# SCH_RDA5807FP_-__2024-04-29.net
KiCad netlist of a schematic drawn in EasyEDA
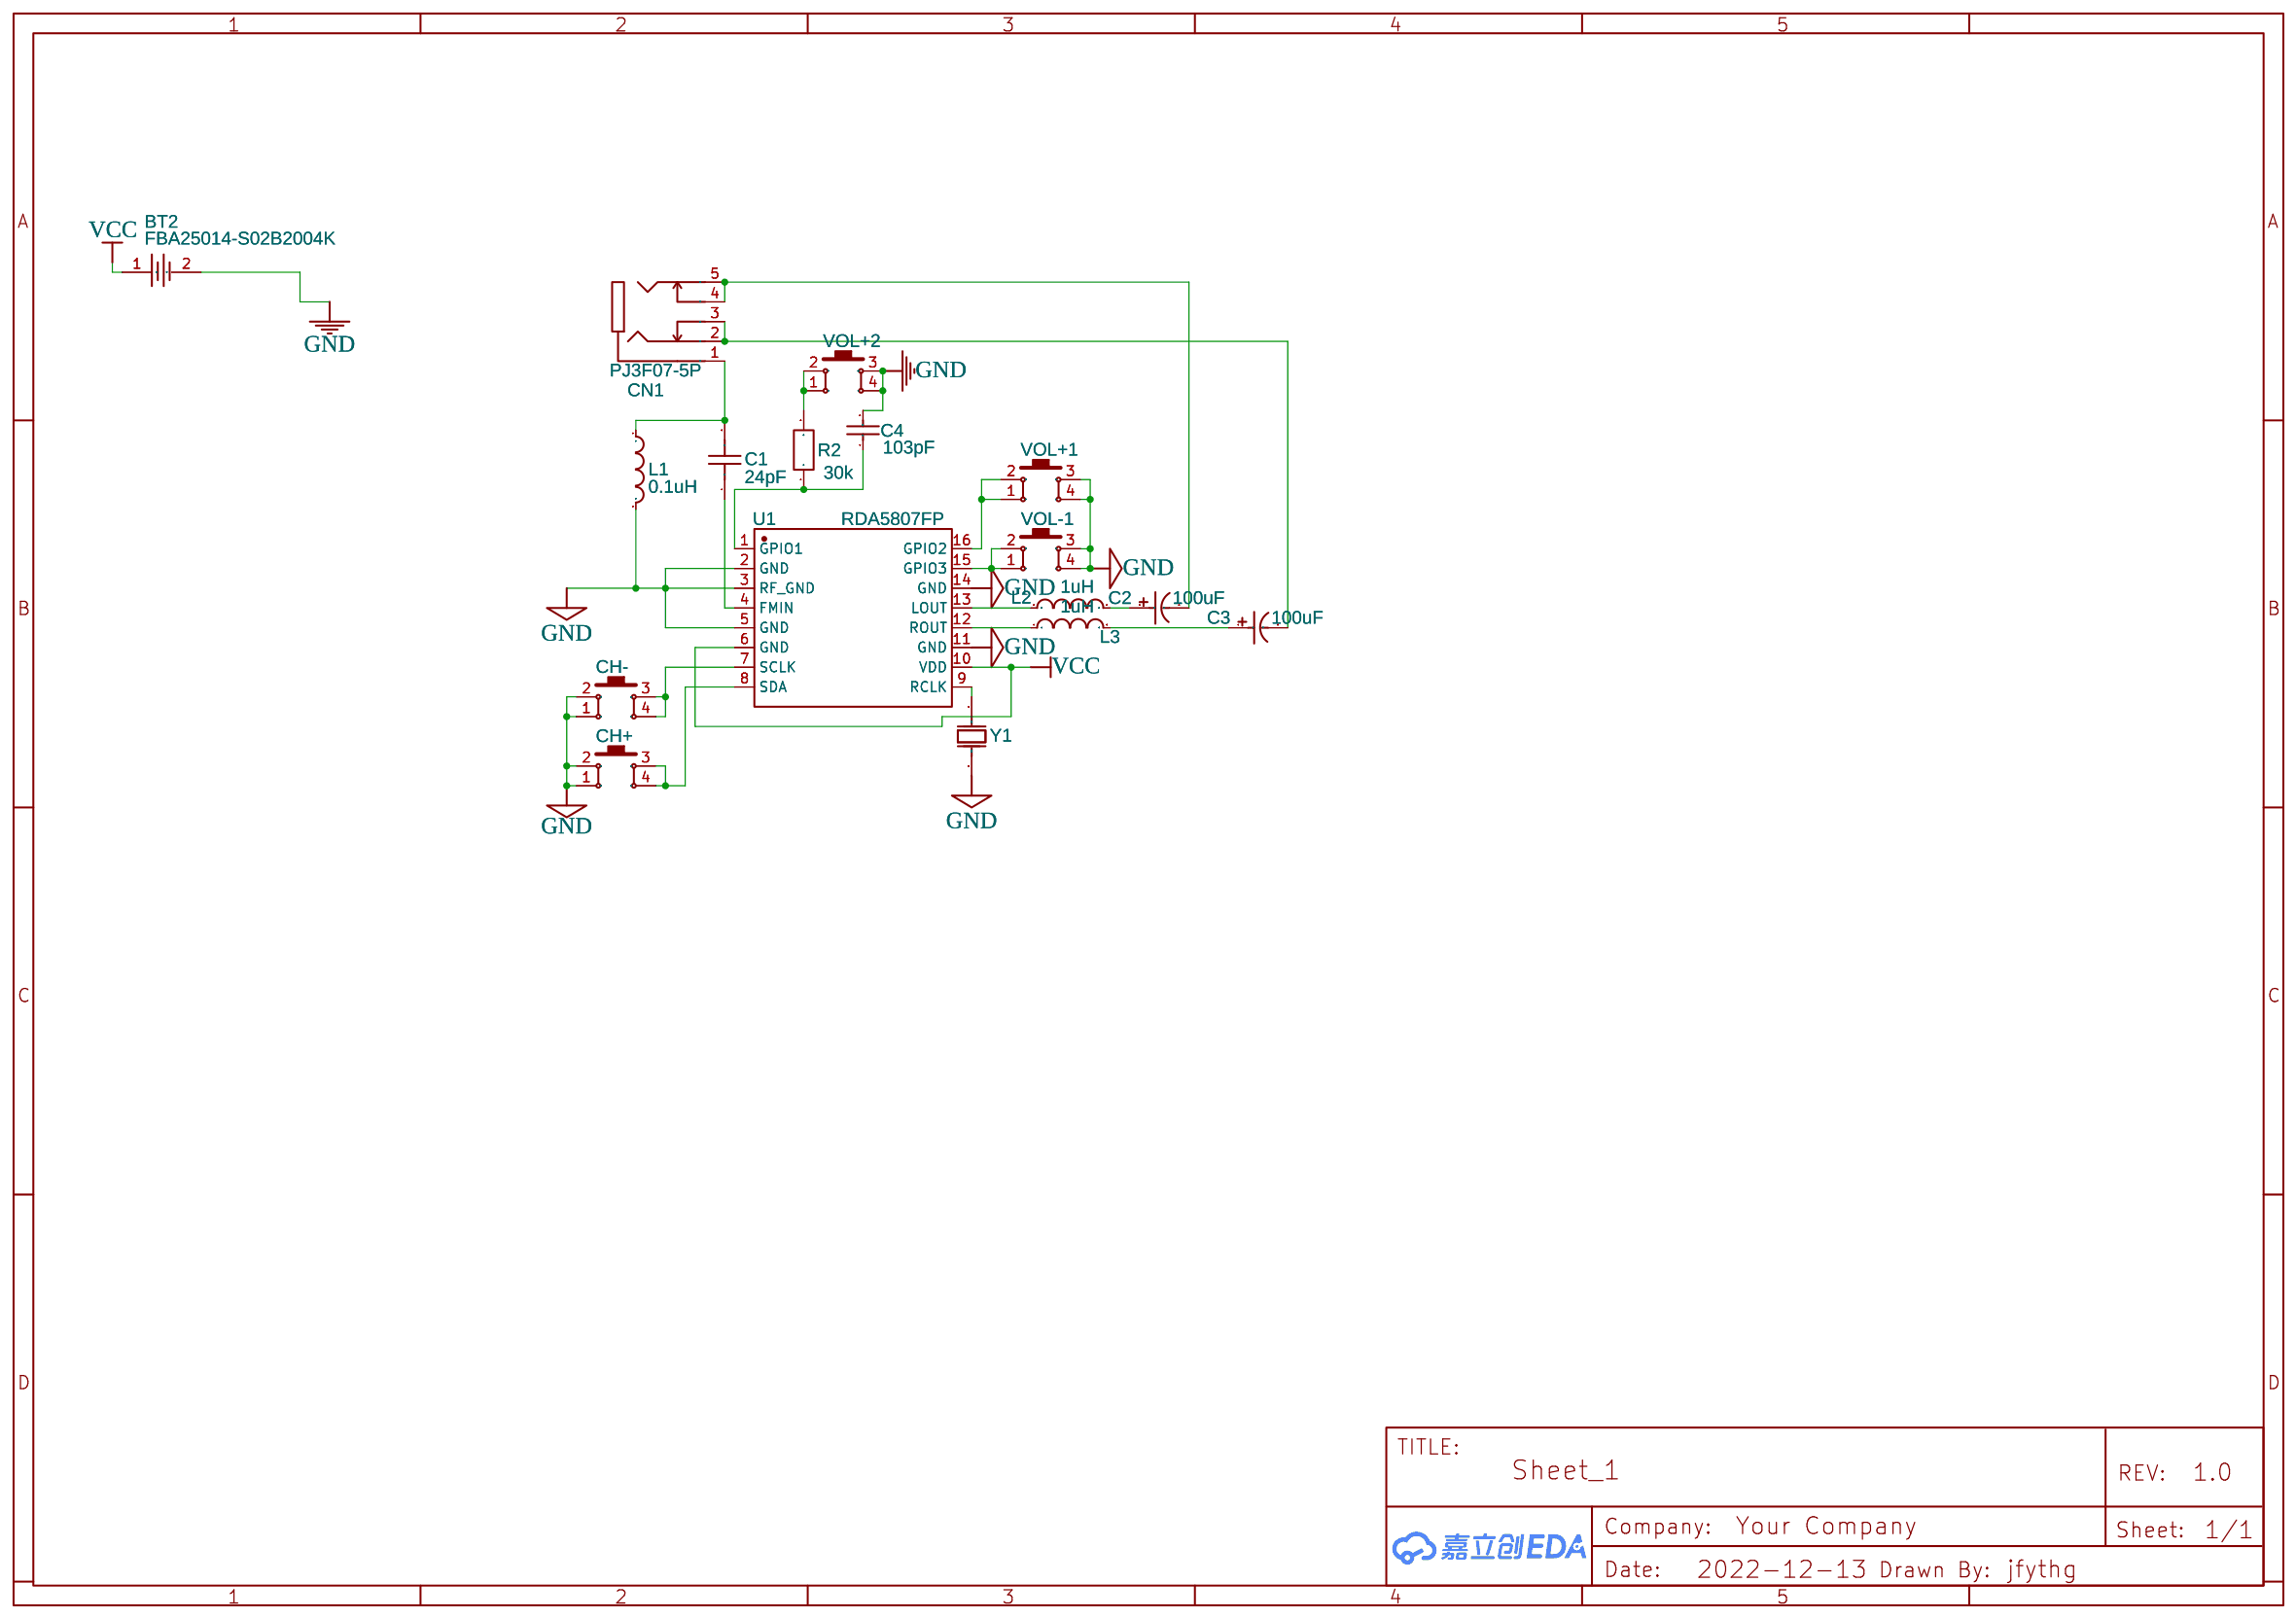
[diagram p0: schematic sheet]

(export (version "E")
  (design (tool "Eeschema 10.0.6"))
  (components
    (comp (ref "BT2")
      (value "FBA25014-S02B2004K")
      (fields (field (name "Manufacturer") "TXGA(特思嘉)"))
      (libsource (lib "") (part "FBA25014-S02B2004K"))
    )
    (comp (ref "C1") (value "24pF") (libsource (lib "") (part "C_0805_US")))
    (comp (ref "C2")
      (value "100uF")
      (fields
        (field (name "Manufacturer Part") "KM107M050F12RR0VH2FP0")
        (field (name "Manufacturer") "CX(承兴)")
      )
      (libsource (lib "") (part "ERR1EM101E11OT"))
    )
    (comp (ref "C3")
      (value "100uF")
      (fields
        (field (name "Manufacturer Part") "KM107M050F12RR0VH2FP0")
        (field (name "Manufacturer") "CX(承兴)")
      )
      (libsource (lib "") (part "ERR1EM101E11OT"))
    )
    (comp (ref "C4") (value "103pF") (libsource (lib "") (part "无极性电容")))
    (comp (ref "CH+")
      (value "按键开关")
      (fields
        (field (name "Manufacturer Part") "TS-1095PD-A9B3-D2")
        (field (name "Manufacturer") "Yuandi(台湾元迪)")
      )
      (libsource (lib "") (part "按键开关_1"))
    )
    (comp (ref "CH-")
      (value "按键开关")
      (fields
        (field (name "Manufacturer Part") "TS-1095PD-A9B3-D2")
        (field (name "Manufacturer") "Yuandi(台湾元迪)")
      )
      (libsource (lib "") (part "按键开关"))
    )
    (comp (ref "CN1")
      (value "PJ3F07-5P")
      (fields (field (name "Manufacturer") "SHOU HAN"))
      (libsource (lib "") (part "PJ3F07-5P"))
    )
    (comp (ref "L1") (value "0.1uH") (libsource (lib "") (part "L0805_US_1")))
    (comp (ref "L2") (value "1uH") (libsource (lib "") (part "L0805_US")))
    (comp (ref "L3") (value "1uH") (libsource (lib "") (part "L0805_US")))
    (comp (ref "R2")
      (value "30k")
      (fields (field (name "Manufacturer Part") "CFR03SJ0511A20") (field (name "Manufacturer") "UniOhm"))
      (libsource (lib "") (part "直插电阻"))
    )
    (comp (ref "U1")
      (value "RDA5807FP")
      (fields (field (name "Manufacturer") "RDA Microelectronics"))
      (libsource (lib "") (part "RDA5807FP"))
    )
    (comp (ref "VOL+1")
      (value "按键开关")
      (fields
        (field (name "Manufacturer Part") "TS-1095PD-A9B3-D2")
        (field (name "Manufacturer") "Yuandi(台湾元迪)")
      )
      (libsource (lib "") (part "按键开关_2"))
    )
    (comp (ref "VOL+2")
      (value "按键开关")
      (fields
        (field (name "Manufacturer Part") "TS-1095PD-A9B3-D2")
        (field (name "Manufacturer") "Yuandi(台湾元迪)")
      )
      (libsource (lib "") (part "按键开关_2"))
    )
    (comp (ref "VOL-1")
      (value "按键开关")
      (fields
        (field (name "Manufacturer Part") "TS-1095PD-A9B3-D2")
        (field (name "Manufacturer") "Yuandi(台湾元迪)")
      )
      (libsource (lib "") (part "按键开关_3"))
    )
    (comp (ref "Y1")
      (value "32.768KHz")
      (fields
        (field (name "Manufacturer Part") "TAXD32768K2BGDAZT2T")
        (field (name "Manufacturer") "Zhejiang Abel Elec")
      )
      (libsource (lib "") (part "TDXLF-206 32.768KHZ 12.5PF 20PPM"))
    )
  )
  (nets
    (net (code "1") (name "GND") (class "Default")
      (node (ref "BT2") (pin "2") (pinfunction "2_2") (pintype "input"))
      (node (ref "C4") (pin "2") (pinfunction "2_2") (pintype "input"))
      (node (ref "CH+") (pin "1") (pinfunction "1_1") (pintype "unspecified"))
      (node (ref "CH+") (pin "2") (pinfunction "2_2") (pintype "unspecified"))
      (node (ref "CH-") (pin "1") (pinfunction "1_1") (pintype "unspecified"))
      (node (ref "CH-") (pin "2") (pinfunction "2_2") (pintype "unspecified"))
      (node (ref "L1") (pin "2") (pinfunction "2_2") (pintype "unspecified"))
      (node (ref "U1") (pin "11") (pinfunction "GND_11") (pintype "unspecified"))
      (node (ref "U1") (pin "14") (pinfunction "GND_14") (pintype "unspecified"))
      (node (ref "U1") (pin "2") (pinfunction "GND_2") (pintype "unspecified"))
      (node (ref "U1") (pin "3") (pinfunction "RF_GND_3") (pintype "unspecified"))
      (node (ref "U1") (pin "5") (pinfunction "GND_5") (pintype "unspecified"))
      (node (ref "VOL+1") (pin "3") (pinfunction "3_3") (pintype "unspecified"))
      (node (ref "VOL+1") (pin "4") (pinfunction "4_4") (pintype "unspecified"))
      (node (ref "VOL+2") (pin "3") (pinfunction "3_3") (pintype "unspecified"))
      (node (ref "VOL+2") (pin "4") (pinfunction "4_4") (pintype "unspecified"))
      (node (ref "VOL-1") (pin "3") (pinfunction "3_3") (pintype "unspecified"))
      (node (ref "VOL-1") (pin "4") (pinfunction "4_4") (pintype "unspecified"))
      (node (ref "Y1") (pin "2") (pinfunction "OSC2_2") (pintype "input"))
    )
    (net (code "2") (name "Net-(C2-Pad1)") (class "Default")
      (node (ref "C2") (pin "1") (pinfunction "1_1") (pintype "input"))
      (node (ref "L2") (pin "2") (pinfunction "2_2") (pintype "unspecified"))
    )
    (net (code "3") (name "Net-(C3-Pad1)") (class "Default")
      (node (ref "C3") (pin "1") (pinfunction "1_1") (pintype "input"))
      (node (ref "L3") (pin "2") (pinfunction "2_2") (pintype "unspecified"))
    )
    (net (code "4") (name "Net-(CN1-A)") (class "Default")
      (node (ref "C1") (pin "2") (pinfunction "2_2") (pintype "unspecified"))
      (node (ref "CN1") (pin "1") (pinfunction "A_1") (pintype "input"))
      (node (ref "L1") (pin "1") (pinfunction "1_1") (pintype "unspecified"))
    )
    (net (code "5") (name "Net-(CN1-B)") (class "Default")
      (node (ref "C3") (pin "2") (pinfunction "2_2") (pintype "input"))
      (node (ref "CN1") (pin "2") (pinfunction "B_2") (pintype "input"))
      (node (ref "CN1") (pin "3") (pinfunction "C_3") (pintype "input"))
    )
    (net (code "6") (name "Net-(CN1-D)") (class "Default")
      (node (ref "C2") (pin "2") (pinfunction "2_2") (pintype "input"))
      (node (ref "CN1") (pin "4") (pinfunction "D_4") (pintype "input"))
      (node (ref "CN1") (pin "5") (pinfunction "E_5") (pintype "input"))
    )
    (net (code "7") (name "Net-(R2-Pad2)") (class "Default")
      (node (ref "R2") (pin "2") (pinfunction "2_2") (pintype "input"))
      (node (ref "VOL+2") (pin "1") (pinfunction "1_1") (pintype "unspecified"))
      (node (ref "VOL+2") (pin "2") (pinfunction "2_2") (pintype "unspecified"))
    )
    (net (code "8") (name "Net-(U1-FMIN)") (class "Default")
      (node (ref "C1") (pin "1") (pinfunction "1_1") (pintype "unspecified"))
      (node (ref "U1") (pin "4") (pinfunction "FMIN_4") (pintype "unspecified"))
    )
    (net (code "9") (name "Net-(U1-GPIO1)") (class "Default")
      (node (ref "C4") (pin "1") (pinfunction "1_1") (pintype "input"))
      (node (ref "R2") (pin "1") (pinfunction "1_1") (pintype "input"))
      (node (ref "U1") (pin "1") (pinfunction "GPIO1_1") (pintype "unspecified"))
    )
    (net (code "10") (name "Net-(U1-GPIO2)") (class "Default")
      (node (ref "U1") (pin "16") (pinfunction "GPIO2_16") (pintype "unspecified"))
      (node (ref "VOL+1") (pin "1") (pinfunction "1_1") (pintype "unspecified"))
      (node (ref "VOL+1") (pin "2") (pinfunction "2_2") (pintype "unspecified"))
    )
    (net (code "11") (name "Net-(U1-GPIO3)") (class "Default")
      (node (ref "U1") (pin "15") (pinfunction "GPIO3_15") (pintype "unspecified"))
      (node (ref "VOL-1") (pin "1") (pinfunction "1_1") (pintype "unspecified"))
      (node (ref "VOL-1") (pin "2") (pinfunction "2_2") (pintype "unspecified"))
    )
    (net (code "12") (name "Net-(U1-LOUT)") (class "Default")
      (node (ref "L2") (pin "1") (pinfunction "1_1") (pintype "unspecified"))
      (node (ref "U1") (pin "13") (pinfunction "LOUT_13") (pintype "unspecified"))
    )
    (net (code "13") (name "Net-(U1-RCLK)") (class "Default")
      (node (ref "U1") (pin "9") (pinfunction "RCLK_9") (pintype "unspecified"))
      (node (ref "Y1") (pin "1") (pinfunction "OSC1_1") (pintype "input"))
    )
    (net (code "14") (name "Net-(U1-ROUT)") (class "Default")
      (node (ref "L3") (pin "1") (pinfunction "1_1") (pintype "unspecified"))
      (node (ref "U1") (pin "12") (pinfunction "ROUT_12") (pintype "unspecified"))
    )
    (net (code "15") (name "Net-(U1-SCLK)") (class "Default")
      (node (ref "CH-") (pin "3") (pinfunction "3_3") (pintype "unspecified"))
      (node (ref "CH-") (pin "4") (pinfunction "4_4") (pintype "unspecified"))
      (node (ref "U1") (pin "7") (pinfunction "SCLK_7") (pintype "unspecified"))
    )
    (net (code "16") (name "Net-(U1-SDA)") (class "Default")
      (node (ref "CH+") (pin "3") (pinfunction "3_3") (pintype "unspecified"))
      (node (ref "CH+") (pin "4") (pinfunction "4_4") (pintype "unspecified"))
      (node (ref "U1") (pin "8") (pinfunction "SDA_8") (pintype "unspecified"))
    )
    (net (code "17") (name "VCC") (class "Default")
      (node (ref "BT2") (pin "1") (pinfunction "1_1") (pintype "input"))
      (node (ref "U1") (pin "10") (pinfunction "VDD_10") (pintype "unspecified"))
      (node (ref "U1") (pin "6") (pinfunction "GND_6") (pintype "unspecified"))
    )
  )
)
